# four_channel_audio_mixer.net
KiCad netlist of a schematic drawn in EAGLE
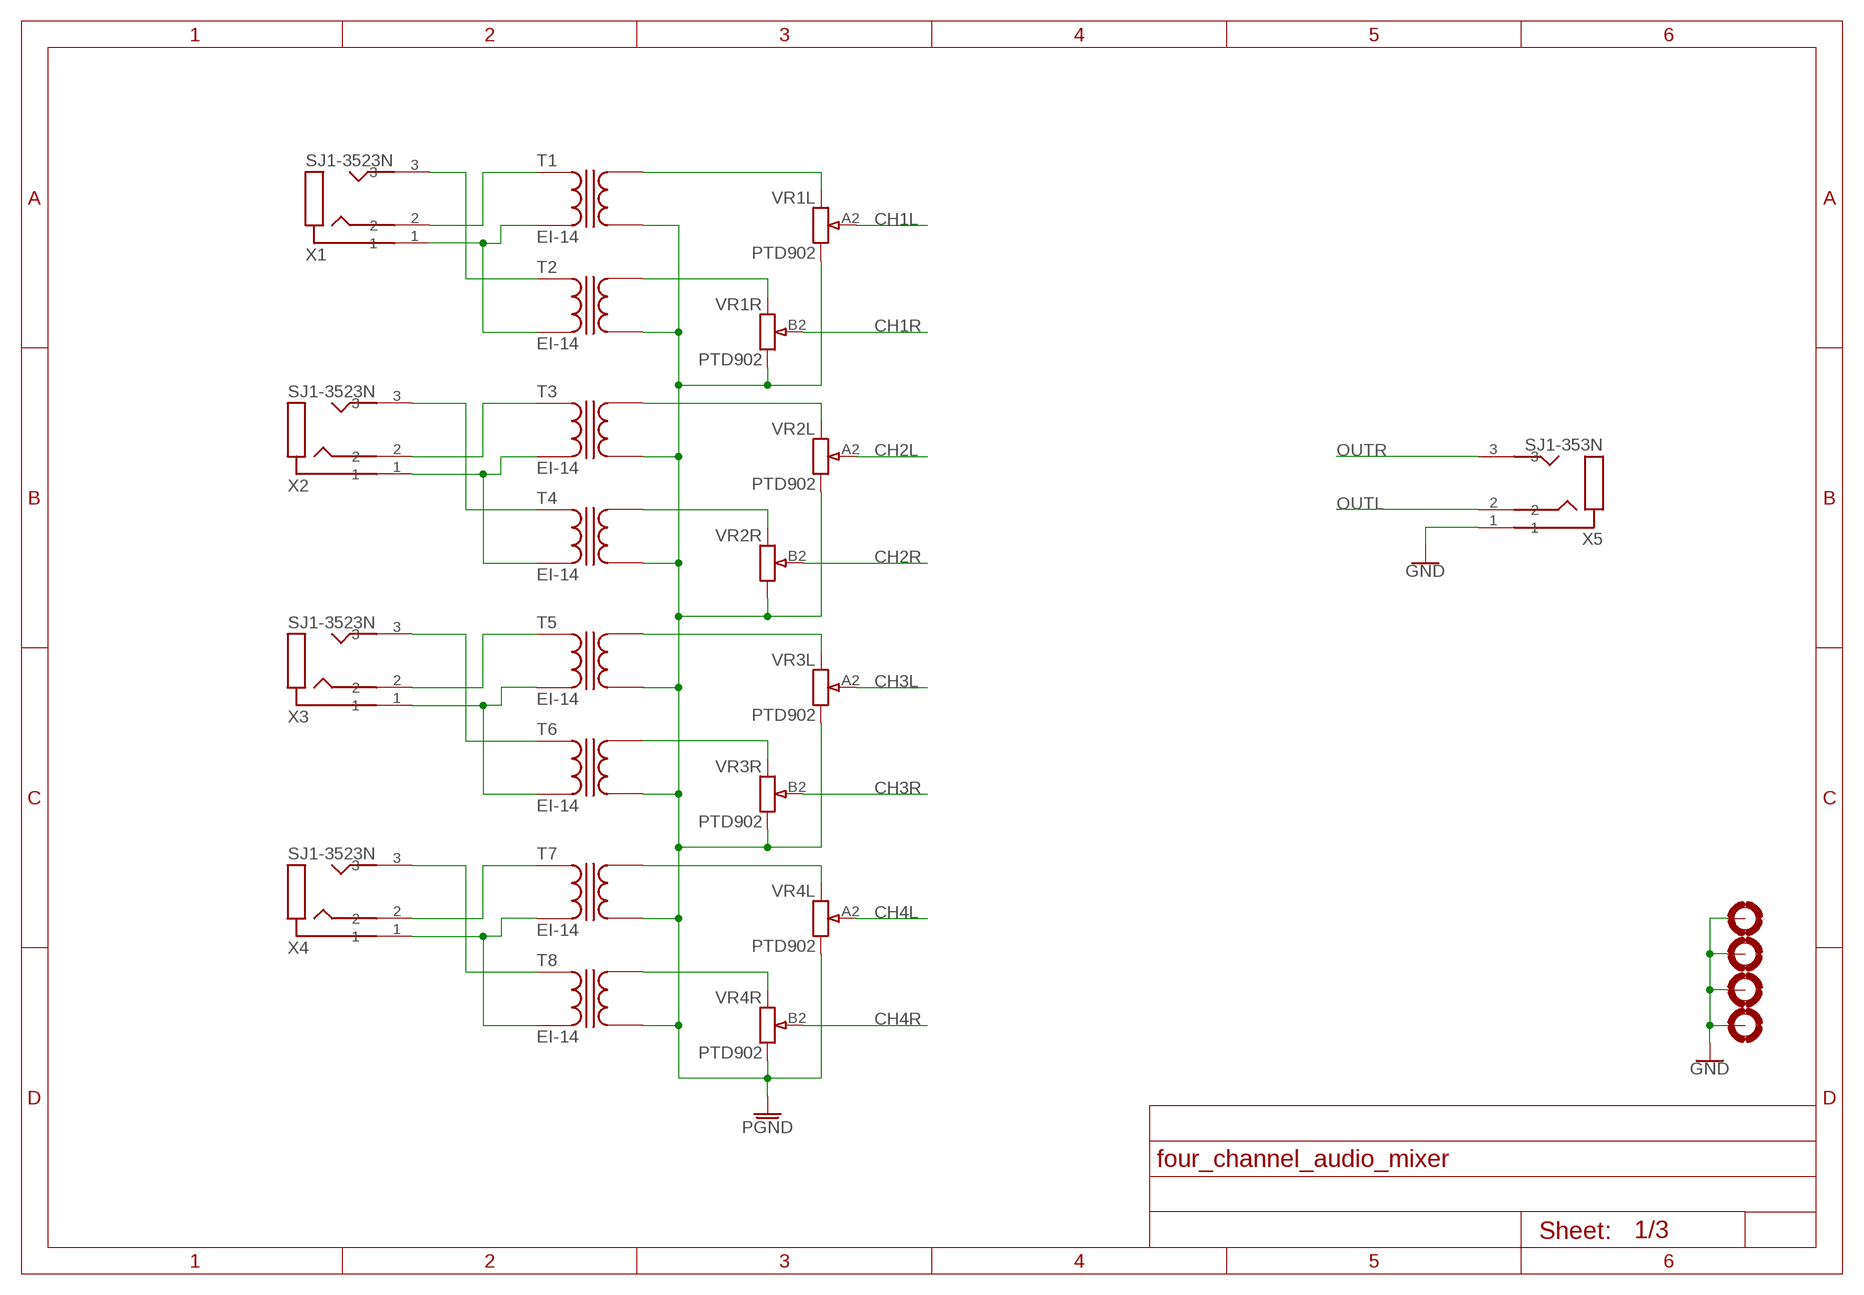
[diagram p0: schematic, sheet 1]
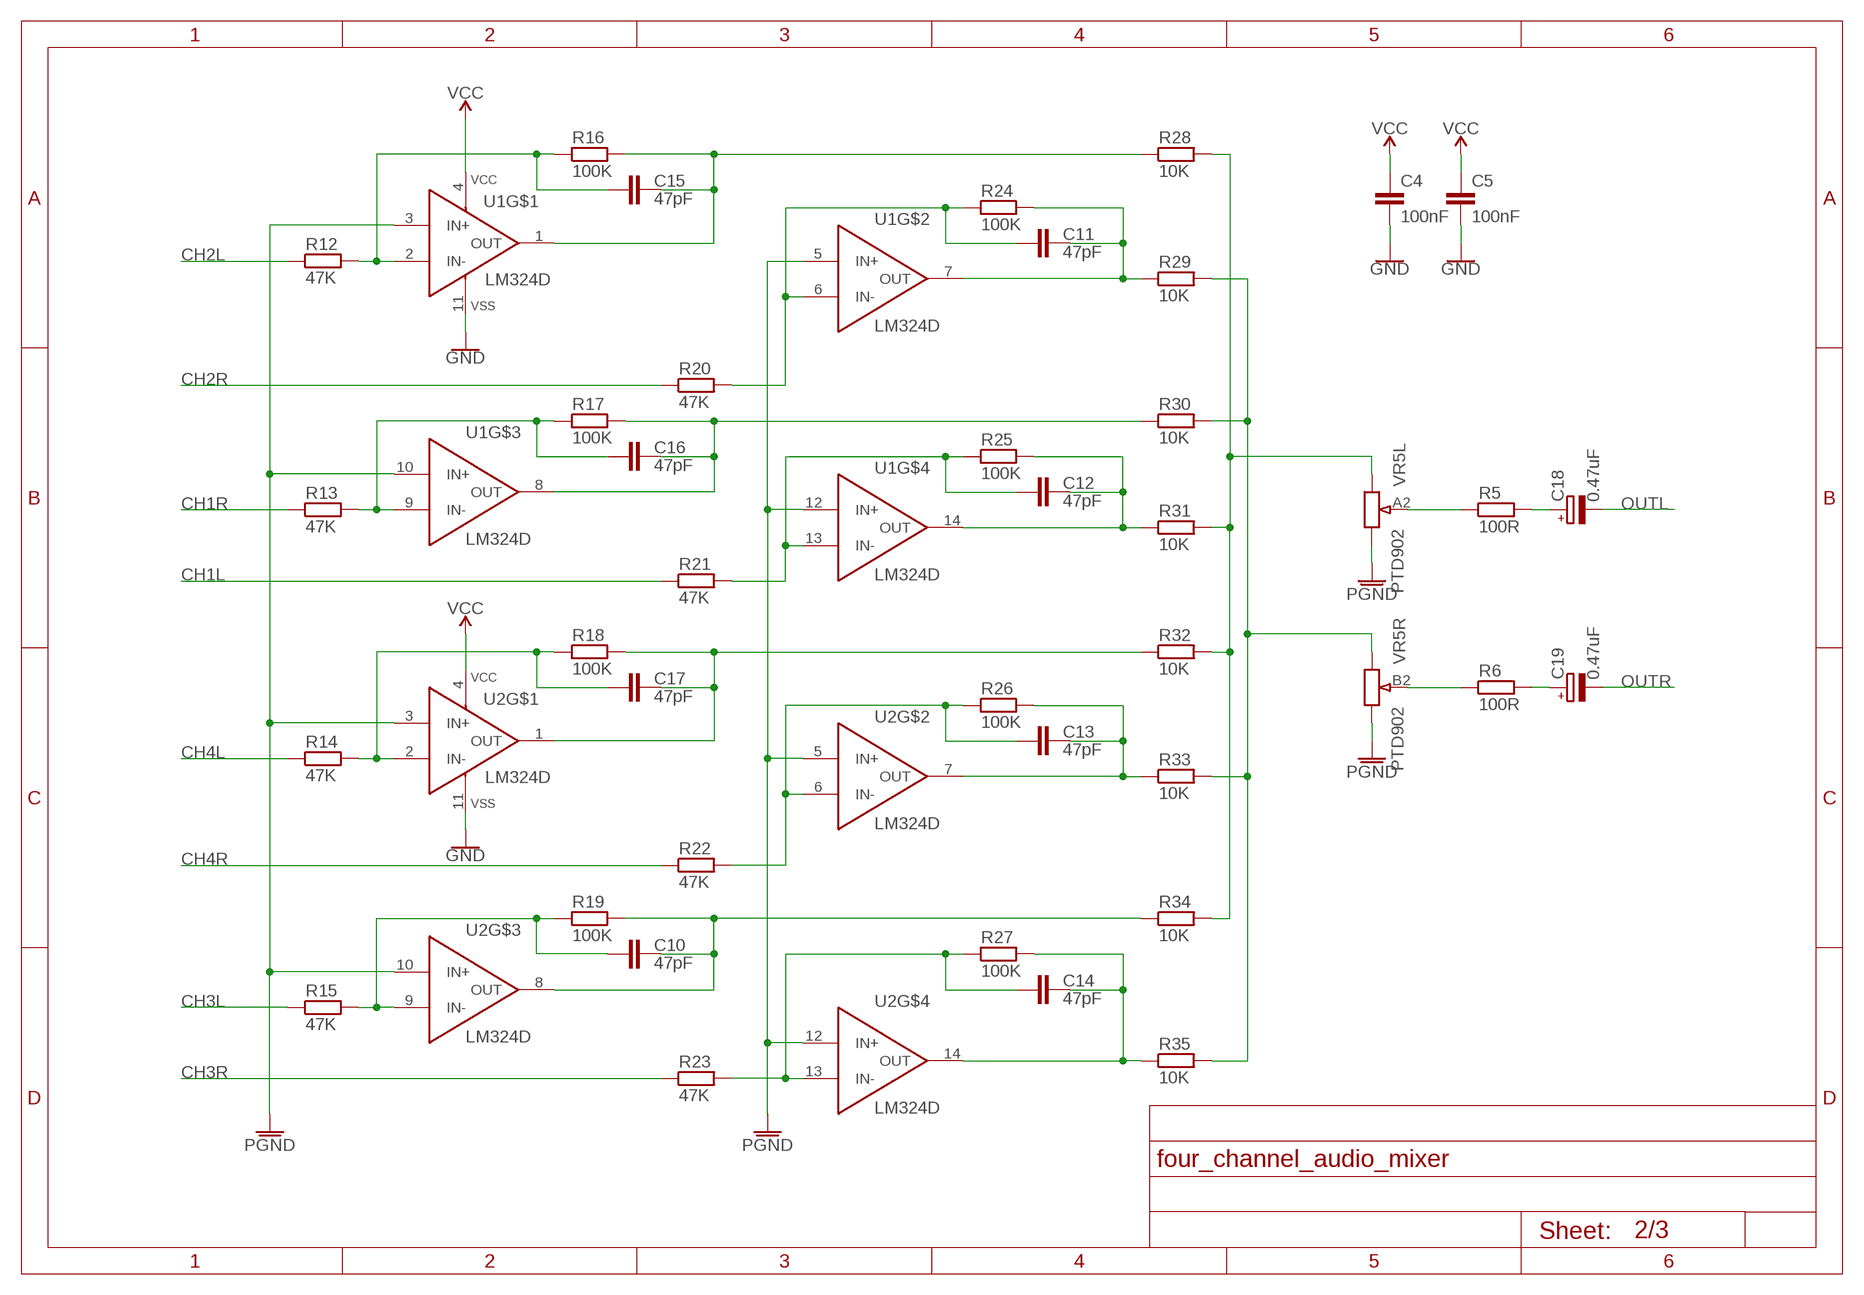
[diagram p1: schematic, sheet 2]
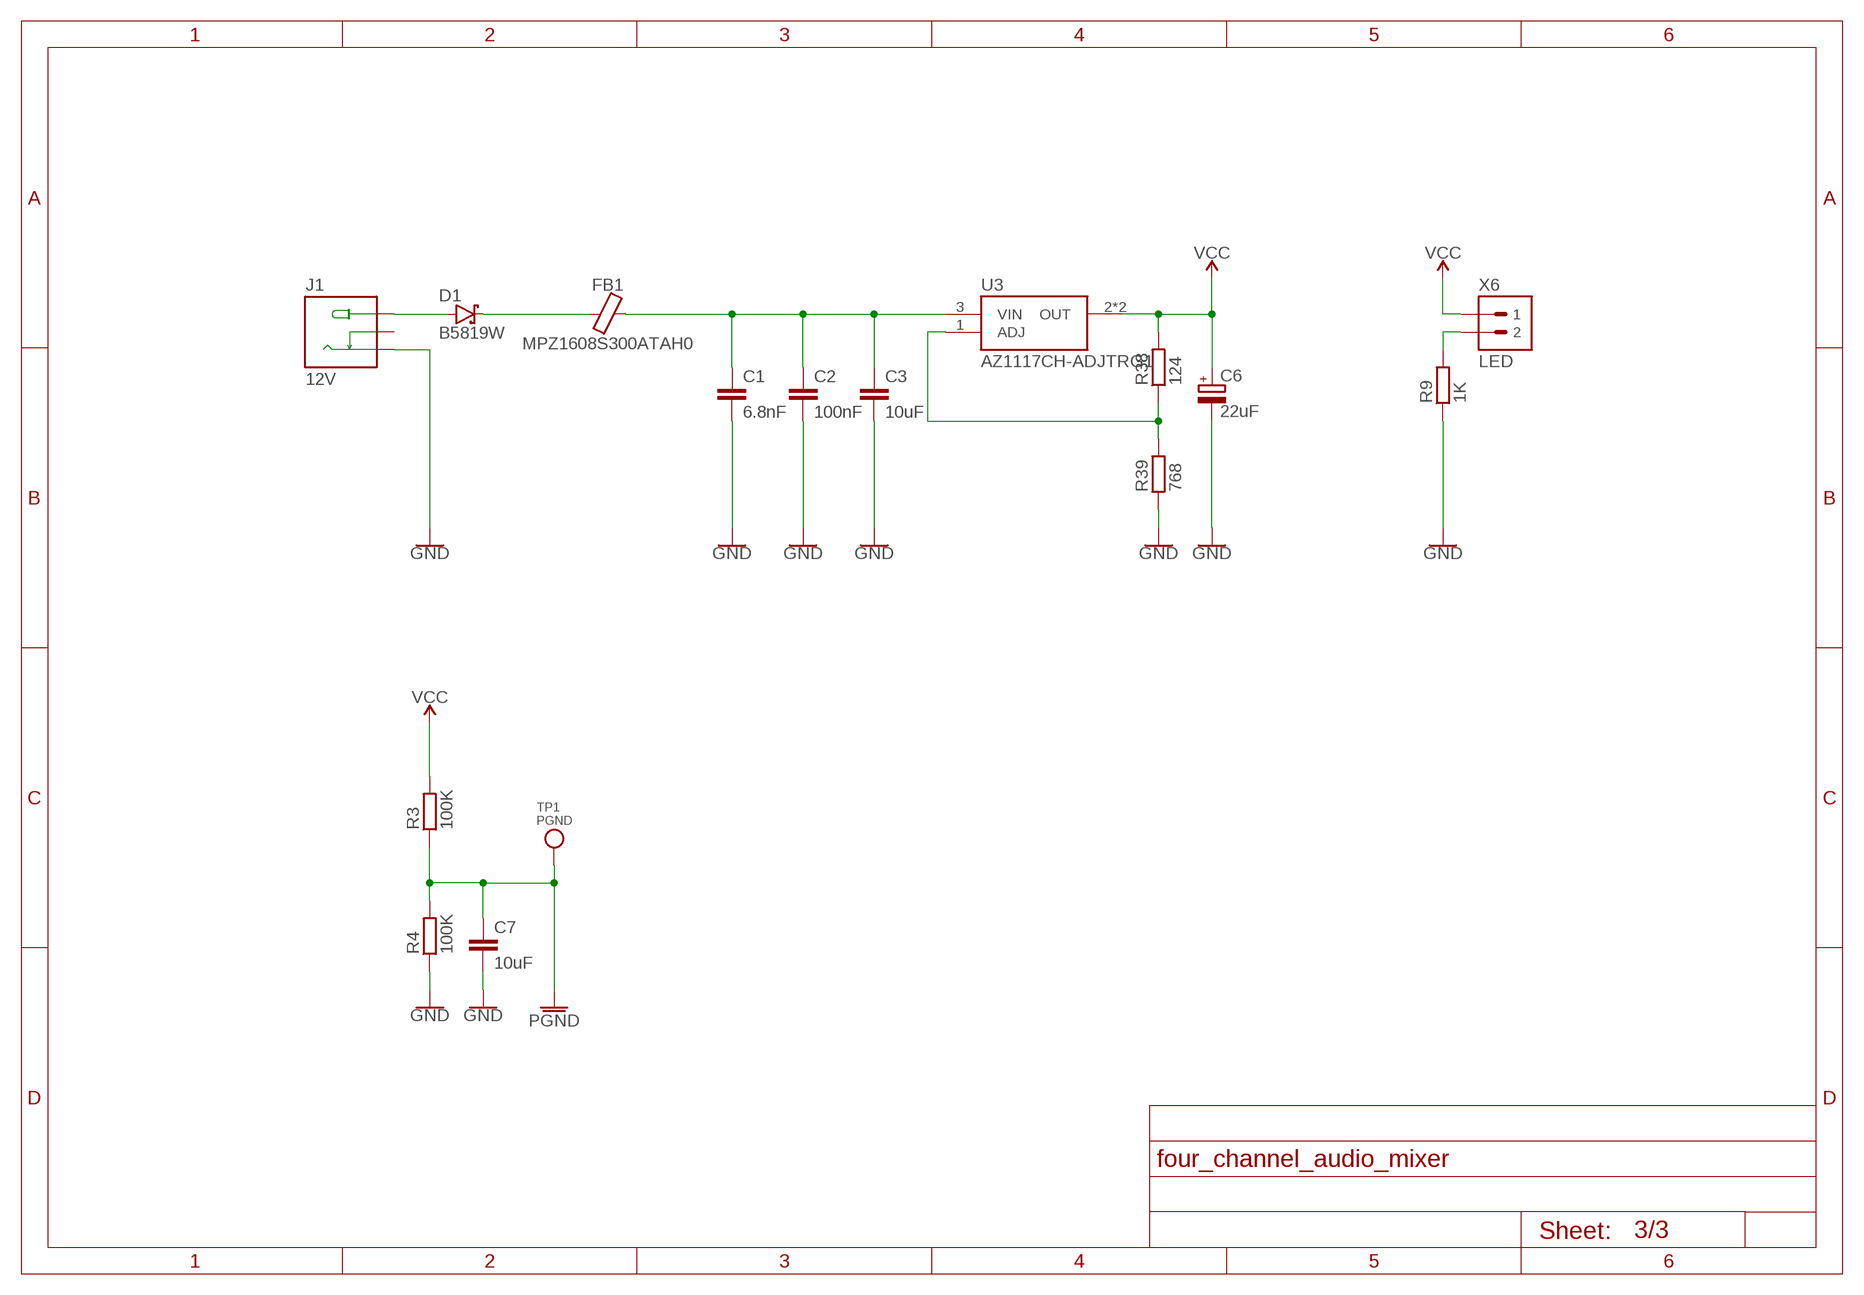
[diagram p2: schematic, sheet 3]

(export (version "E")
  (design (tool "Eeschema 10.0.6"))
  (components
    (comp (ref "H1")
      (value "MOUNTHOLE-PAD3.2")
      (footprint "eagle-import:3.2-PAD")
      (libsource (lib "eagle-import") (part "MOUNTHOLE-PAD3.2"))
    )
    (comp (ref "H2")
      (value "MOUNTHOLE-PAD3.2")
      (footprint "eagle-import:3.2-PAD")
      (libsource (lib "eagle-import") (part "MOUNTHOLE-PAD3.2"))
    )
    (comp (ref "H3")
      (value "MOUNTHOLE-PAD3.2")
      (footprint "eagle-import:3.2-PAD")
      (libsource (lib "eagle-import") (part "MOUNTHOLE-PAD3.2"))
    )
    (comp (ref "H4")
      (value "MOUNTHOLE-PAD3.2")
      (footprint "eagle-import:3.2-PAD")
      (libsource (lib "eagle-import") (part "MOUNTHOLE-PAD3.2"))
    )
    (comp (ref "T1")
      (value "EI-14")
      (footprint "eagle-import:TRANSFORMER_EI14")
      (libsource (lib "eagle-import") (part "TRANSFORMEREI14"))
    )
    (comp (ref "T2")
      (value "EI-14")
      (footprint "eagle-import:TRANSFORMER_EI14")
      (libsource (lib "eagle-import") (part "TRANSFORMEREI14"))
    )
    (comp (ref "T3")
      (value "EI-14")
      (footprint "eagle-import:TRANSFORMER_EI14")
      (libsource (lib "eagle-import") (part "TRANSFORMEREI14"))
    )
    (comp (ref "T4")
      (value "EI-14")
      (footprint "eagle-import:TRANSFORMER_EI14")
      (libsource (lib "eagle-import") (part "TRANSFORMEREI14"))
    )
    (comp (ref "T5")
      (value "EI-14")
      (footprint "eagle-import:TRANSFORMER_EI14")
      (libsource (lib "eagle-import") (part "TRANSFORMEREI14"))
    )
    (comp (ref "T6")
      (value "EI-14")
      (footprint "eagle-import:TRANSFORMER_EI14")
      (libsource (lib "eagle-import") (part "TRANSFORMEREI14"))
    )
    (comp (ref "T7")
      (value "EI-14")
      (footprint "eagle-import:TRANSFORMER_EI14")
      (libsource (lib "eagle-import") (part "TRANSFORMEREI14"))
    )
    (comp (ref "T8")
      (value "EI-14")
      (footprint "eagle-import:TRANSFORMER_EI14")
      (libsource (lib "eagle-import") (part "TRANSFORMEREI14"))
    )
    (comp (ref "VR1")
      (value "PTD902")
      (footprint "eagle-import:POT-PTD902")
      (libsource (lib "eagle-import") (part "POT-PTD902"))
    )
    (comp (ref "VR2")
      (value "PTD902")
      (footprint "eagle-import:POT-PTD902")
      (libsource (lib "eagle-import") (part "POT-PTD902"))
    )
    (comp (ref "VR3")
      (value "PTD902")
      (footprint "eagle-import:POT-PTD902")
      (libsource (lib "eagle-import") (part "POT-PTD902"))
    )
    (comp (ref "VR4")
      (value "PTD902")
      (footprint "eagle-import:POT-PTD902")
      (libsource (lib "eagle-import") (part "POT-PTD902"))
    )
    (comp (ref "X1")
      (value "SJ1-3523N")
      (footprint "eagle-import:AUDIO-3.5-SJ1-3523N")
      (libsource (lib "eagle-import") (part "AUDIO-3.5-SJ1-3523N"))
    )
    (comp (ref "X2")
      (value "SJ1-3523N")
      (footprint "eagle-import:AUDIO-3.5-SJ1-3523N")
      (libsource (lib "eagle-import") (part "AUDIO-3.5-SJ1-3523N"))
    )
    (comp (ref "X3")
      (value "SJ1-3523N")
      (footprint "eagle-import:AUDIO-3.5-SJ1-3523N")
      (libsource (lib "eagle-import") (part "AUDIO-3.5-SJ1-3523N"))
    )
    (comp (ref "X4")
      (value "SJ1-3523N")
      (footprint "eagle-import:AUDIO-3.5-SJ1-3523N")
      (libsource (lib "eagle-import") (part "AUDIO-3.5-SJ1-3523N"))
    )
    (comp (ref "X5")
      (value "SJ1-353N")
      (footprint "eagle-import:AUDIO-3.5-SJ1-3523N")
      (libsource (lib "eagle-import") (part "AUDIO-3.5-SJ1-3523N"))
    )
    (comp (ref "C4")
      (value "100nF")
      (footprint "eagle-import:C0603")
      (libsource (lib "eagle-import") (part "CAPC0603"))
    )
    (comp (ref "C5")
      (value "100nF")
      (footprint "eagle-import:C0603")
      (libsource (lib "eagle-import") (part "CAPC0603"))
    )
    (comp (ref "C10")
      (value "47pF")
      (footprint "eagle-import:C0603")
      (libsource (lib "eagle-import") (part "CAPC0603"))
    )
    (comp (ref "C11")
      (value "47pF")
      (footprint "eagle-import:C0603")
      (libsource (lib "eagle-import") (part "CAPC0603"))
    )
    (comp (ref "C12")
      (value "47pF")
      (footprint "eagle-import:C0603")
      (libsource (lib "eagle-import") (part "CAPC0603"))
    )
    (comp (ref "C13")
      (value "47pF")
      (footprint "eagle-import:C0603")
      (libsource (lib "eagle-import") (part "CAPC0603"))
    )
    (comp (ref "C14")
      (value "47pF")
      (footprint "eagle-import:C0603")
      (libsource (lib "eagle-import") (part "CAPC0603"))
    )
    (comp (ref "C15")
      (value "47pF")
      (footprint "eagle-import:C0603")
      (libsource (lib "eagle-import") (part "CAPC0603"))
    )
    (comp (ref "C16")
      (value "47pF")
      (footprint "eagle-import:C0603")
      (libsource (lib "eagle-import") (part "CAPC0603"))
    )
    (comp (ref "C17")
      (value "47pF")
      (footprint "eagle-import:C0603")
      (libsource (lib "eagle-import") (part "CAPC0603"))
    )
    (comp (ref "C18")
      (value "0.47uF")
      (footprint "eagle-import:WE-4.0X5.5")
      (libsource (lib "eagle-import") (part "CAP-POL-ALUMWURTH-4.0X5.5"))
    )
    (comp (ref "C19")
      (value "0.47uF")
      (footprint "eagle-import:WE-4.0X5.5")
      (libsource (lib "eagle-import") (part "CAP-POL-ALUMWURTH-4.0X5.5"))
    )
    (comp (ref "R5")
      (value "100R")
      (footprint "eagle-import:R0603")
      (libsource (lib "eagle-import") (part "RESISTOR0603"))
    )
    (comp (ref "R6")
      (value "100R")
      (footprint "eagle-import:R0603")
      (libsource (lib "eagle-import") (part "RESISTOR0603"))
    )
    (comp (ref "R12")
      (value "47K")
      (footprint "eagle-import:R0603")
      (libsource (lib "eagle-import") (part "RESISTOR0603"))
    )
    (comp (ref "R13")
      (value "47K")
      (footprint "eagle-import:R0603")
      (libsource (lib "eagle-import") (part "RESISTOR0603"))
    )
    (comp (ref "R14")
      (value "47K")
      (footprint "eagle-import:R0603")
      (libsource (lib "eagle-import") (part "RESISTOR0603"))
    )
    (comp (ref "R15")
      (value "47K")
      (footprint "eagle-import:R0603")
      (libsource (lib "eagle-import") (part "RESISTOR0603"))
    )
    (comp (ref "R16")
      (value "100K")
      (footprint "eagle-import:R0603")
      (libsource (lib "eagle-import") (part "RESISTOR0603"))
    )
    (comp (ref "R17")
      (value "100K")
      (footprint "eagle-import:R0603")
      (libsource (lib "eagle-import") (part "RESISTOR0603"))
    )
    (comp (ref "R18")
      (value "100K")
      (footprint "eagle-import:R0603")
      (libsource (lib "eagle-import") (part "RESISTOR0603"))
    )
    (comp (ref "R19")
      (value "100K")
      (footprint "eagle-import:R0603")
      (libsource (lib "eagle-import") (part "RESISTOR0603"))
    )
    (comp (ref "R20")
      (value "47K")
      (footprint "eagle-import:R0603")
      (libsource (lib "eagle-import") (part "RESISTOR0603"))
    )
    (comp (ref "R21")
      (value "47K")
      (footprint "eagle-import:R0603")
      (libsource (lib "eagle-import") (part "RESISTOR0603"))
    )
    (comp (ref "R22")
      (value "47K")
      (footprint "eagle-import:R0603")
      (libsource (lib "eagle-import") (part "RESISTOR0603"))
    )
    (comp (ref "R23")
      (value "47K")
      (footprint "eagle-import:R0603")
      (libsource (lib "eagle-import") (part "RESISTOR0603"))
    )
    (comp (ref "R24")
      (value "100K")
      (footprint "eagle-import:R0603")
      (libsource (lib "eagle-import") (part "RESISTOR0603"))
    )
    (comp (ref "R25")
      (value "100K")
      (footprint "eagle-import:R0603")
      (libsource (lib "eagle-import") (part "RESISTOR0603"))
    )
    (comp (ref "R26")
      (value "100K")
      (footprint "eagle-import:R0603")
      (libsource (lib "eagle-import") (part "RESISTOR0603"))
    )
    (comp (ref "R27")
      (value "100K")
      (footprint "eagle-import:R0603")
      (libsource (lib "eagle-import") (part "RESISTOR0603"))
    )
    (comp (ref "R28")
      (value "10K")
      (footprint "eagle-import:R0603")
      (libsource (lib "eagle-import") (part "RESISTOR0603"))
    )
    (comp (ref "R29")
      (value "10K")
      (footprint "eagle-import:R0603")
      (libsource (lib "eagle-import") (part "RESISTOR0603"))
    )
    (comp (ref "R30")
      (value "10K")
      (footprint "eagle-import:R0603")
      (libsource (lib "eagle-import") (part "RESISTOR0603"))
    )
    (comp (ref "R31")
      (value "10K")
      (footprint "eagle-import:R0603")
      (libsource (lib "eagle-import") (part "RESISTOR0603"))
    )
    (comp (ref "R32")
      (value "10K")
      (footprint "eagle-import:R0603")
      (libsource (lib "eagle-import") (part "RESISTOR0603"))
    )
    (comp (ref "R33")
      (value "10K")
      (footprint "eagle-import:R0603")
      (libsource (lib "eagle-import") (part "RESISTOR0603"))
    )
    (comp (ref "R34")
      (value "10K")
      (footprint "eagle-import:R0603")
      (libsource (lib "eagle-import") (part "RESISTOR0603"))
    )
    (comp (ref "R35")
      (value "10K")
      (footprint "eagle-import:R0603")
      (libsource (lib "eagle-import") (part "RESISTOR0603"))
    )
    (comp (ref "U1")
      (value "LM324D")
      (footprint "eagle-import:SOIC-14")
      (libsource (lib "eagle-import") (part "OPAMP-LM324D"))
    )
    (comp (ref "U2")
      (value "LM324D")
      (footprint "eagle-import:SOIC-14")
      (libsource (lib "eagle-import") (part "OPAMP-LM324D"))
    )
    (comp (ref "VR5")
      (value "PTD902")
      (footprint "eagle-import:POT-PTD902")
      (libsource (lib "eagle-import") (part "POT-PTD902"))
    )
    (comp (ref "C1")
      (value "6.8nF")
      (footprint "eagle-import:C0603")
      (libsource (lib "eagle-import") (part "CAPC0603"))
    )
    (comp (ref "C2")
      (value "100nF")
      (footprint "eagle-import:C0603")
      (libsource (lib "eagle-import") (part "CAPC0603"))
    )
    (comp (ref "C3")
      (value "10uF")
      (footprint "eagle-import:C0603")
      (libsource (lib "eagle-import") (part "CAPC0603"))
    )
    (comp (ref "C6")
      (value "22uF")
      (footprint "eagle-import:CASE-B-3528")
      (libsource (lib "eagle-import") (part "CAP-TANT-HUNANB-3528"))
    )
    (comp (ref "C7")
      (value "10uF")
      (footprint "eagle-import:C0603")
      (libsource (lib "eagle-import") (part "CAPC0603"))
    )
    (comp (ref "D1")
      (value "B5819W")
      (footprint "eagle-import:SOD-123")
      (libsource (lib "eagle-import") (part "DIODE-SCHOTTKYSOD-123"))
    )
    (comp (ref "FB1")
      (value "MPZ1608S300ATAH0")
      (footprint "eagle-import:MPZ1608")
      (libsource (lib "eagle-import") (part "BEADMPZ1608"))
    )
    (comp (ref "J1")
      (value "12V")
      (footprint "eagle-import:5DJ20DC02-03T0BLB-01-14.5X10.7.0X9.0MM")
      (libsource (lib "eagle-import") (part "CONN-POWER-JACK-2.1MM(DC-005)5DJ20DC02"))
    )
    (comp (ref "R3")
      (value "100K")
      (footprint "eagle-import:R0603")
      (libsource (lib "eagle-import") (part "RESISTOR0603"))
    )
    (comp (ref "R4")
      (value "100K")
      (footprint "eagle-import:R0603")
      (libsource (lib "eagle-import") (part "RESISTOR0603"))
    )
    (comp (ref "R9")
      (value "1K")
      (footprint "eagle-import:R0603")
      (libsource (lib "eagle-import") (part "RESISTOR0603"))
    )
    (comp (ref "R38")
      (value "124")
      (footprint "eagle-import:R0603")
      (libsource (lib "eagle-import") (part "RESISTOR0603"))
    )
    (comp (ref "R39")
      (value "768")
      (footprint "eagle-import:R0603")
      (libsource (lib "eagle-import") (part "RESISTOR0603"))
    )
    (comp (ref "TP1")
      (value "PGND")
      (footprint "eagle-import:1X01_ROUND")
      (libsource (lib "eagle-import") (part "TESTPOINT0.1{dblquote}"))
    )
    (comp (ref "U3")
      (value "AZ1117CH-ADJTRG1")
      (footprint "eagle-import:SOT-223")
      (libsource (lib "eagle-import") (part "DIODES-AZ1117CH-ADJTRG1"))
    )
    (comp (ref "X6")
      (value "LED")
      (footprint "eagle-import:1X02P-2.54")
      (libsource (lib "eagle-import") (part "HEADER-1X02-2.54POL"))
    )
  )
  (nets
    (net (code "1") (name "CH1L") (class "Default")
      (node (ref "R21") (pin "1") (pinfunction "1_1") (pintype "passive"))
      (node (ref "VR1") (pin "A2") (pinfunction "2_A2") (pintype "bidirectional"))
    )
    (net (code "2") (name "CH1R") (class "Default")
      (node (ref "R13") (pin "1") (pinfunction "1_1") (pintype "passive"))
      (node (ref "VR1") (pin "B2") (pinfunction "2_B2") (pintype "bidirectional"))
    )
    (net (code "3") (name "CH2L") (class "Default")
      (node (ref "R12") (pin "1") (pinfunction "1_1") (pintype "passive"))
      (node (ref "VR2") (pin "A2") (pinfunction "2_A2") (pintype "bidirectional"))
    )
    (net (code "4") (name "CH2R") (class "Default")
      (node (ref "R20") (pin "1") (pinfunction "1_1") (pintype "passive"))
      (node (ref "VR2") (pin "B2") (pinfunction "2_B2") (pintype "bidirectional"))
    )
    (net (code "5") (name "CH3L") (class "Default")
      (node (ref "R15") (pin "1") (pinfunction "1_1") (pintype "passive"))
      (node (ref "VR3") (pin "A2") (pinfunction "2_A2") (pintype "bidirectional"))
    )
    (net (code "6") (name "CH3R") (class "Default")
      (node (ref "R23") (pin "1") (pinfunction "1_1") (pintype "passive"))
      (node (ref "VR3") (pin "B2") (pinfunction "2_B2") (pintype "bidirectional"))
    )
    (net (code "7") (name "CH4L") (class "Default")
      (node (ref "R14") (pin "1") (pinfunction "1_1") (pintype "passive"))
      (node (ref "VR4") (pin "A2") (pinfunction "2_A2") (pintype "bidirectional"))
    )
    (net (code "8") (name "CH4R") (class "Default")
      (node (ref "R22") (pin "1") (pinfunction "1_1") (pintype "passive"))
      (node (ref "VR4") (pin "B2") (pinfunction "2_B2") (pintype "bidirectional"))
    )
    (net (code "9") (name "GND") (class "Default")
      (node (ref "C1") (pin "2") (pinfunction "2_2") (pintype "passive"))
      (node (ref "C2") (pin "2") (pinfunction "2_2") (pintype "passive"))
      (node (ref "C3") (pin "2") (pinfunction "2_2") (pintype "passive"))
      (node (ref "C4") (pin "2") (pinfunction "2_2") (pintype "passive"))
      (node (ref "C5") (pin "2") (pinfunction "2_2") (pintype "passive"))
      (node (ref "C6") (pin "-") (pinfunction "-_-") (pintype "passive"))
      (node (ref "C7") (pin "2") (pinfunction "2_2") (pintype "passive"))
      (node (ref "H1") (pin "B3,2") (pinfunction "MOUNT_B3,2") (pintype "passive"))
      (node (ref "H2") (pin "B3,2") (pinfunction "MOUNT_B3,2") (pintype "passive"))
      (node (ref "H3") (pin "B3,2") (pinfunction "MOUNT_B3,2") (pintype "passive"))
      (node (ref "H4") (pin "B3,2") (pinfunction "MOUNT_B3,2") (pintype "passive"))
      (node (ref "J1") (pin "-1") (pinfunction "-_-1") (pintype "bidirectional"))
      (node (ref "R39") (pin "1") (pinfunction "1_1") (pintype "passive"))
      (node (ref "R4") (pin "1") (pinfunction "1_1") (pintype "passive"))
      (node (ref "R9") (pin "1") (pinfunction "1_1") (pintype "passive"))
      (node (ref "U1") (pin "11") (pinfunction "VSS_11") (pintype "bidirectional"))
      (node (ref "U2") (pin "11") (pinfunction "VSS_11") (pintype "bidirectional"))
      (node (ref "X5") (pin "1") (pinfunction "1_1") (pintype "bidirectional"))
    )
    (net (code "10") (name "Net-(C18-Pad+)") (class "Default")
      (node (ref "C18") (pin "+") (pinfunction "+_+") (pintype "passive"))
      (node (ref "R5") (pin "2") (pinfunction "2_2") (pintype "passive"))
    )
    (net (code "11") (name "Net-(C19-Pad+)") (class "Default")
      (node (ref "C19") (pin "+") (pinfunction "+_+") (pintype "passive"))
      (node (ref "R6") (pin "2") (pinfunction "2_2") (pintype "passive"))
    )
    (net (code "12") (name "Net-(D1-PadA)") (class "Default")
      (node (ref "D1") (pin "A") (pinfunction "A_A") (pintype "passive"))
      (node (ref "J1") (pin "+") (pinfunction "+_+") (pintype "bidirectional"))
    )
    (net (code "13") (name "Net-(D1-PadC)") (class "Default")
      (node (ref "D1") (pin "C") (pinfunction "C_C") (pintype "passive"))
      (node (ref "FB1") (pin "1") (pinfunction "1_1") (pintype "bidirectional"))
    )
    (net (code "14") (name "Net-(R9-Pad2)") (class "Default")
      (node (ref "R9") (pin "2") (pinfunction "2_2") (pintype "passive"))
      (node (ref "X6") (pin "2") (pinfunction "2_2") (pintype "passive"))
    )
    (net (code "15") (name "Net-(T1-PadA1)") (class "Default")
      (node (ref "T1") (pin "A1") (pinfunction "A1_A1") (pintype "bidirectional"))
      (node (ref "X1") (pin "2") (pinfunction "2_2") (pintype "bidirectional"))
    )
    (net (code "16") (name "Net-(T1-PadA2)") (class "Default")
      (node (ref "T1") (pin "A2") (pinfunction "A2_A2") (pintype "bidirectional"))
      (node (ref "T2") (pin "A2") (pinfunction "A2_A2") (pintype "bidirectional"))
      (node (ref "X1") (pin "1") (pinfunction "1_1") (pintype "bidirectional"))
    )
    (net (code "17") (name "Net-(T2-PadA1)") (class "Default")
      (node (ref "T2") (pin "A1") (pinfunction "A1_A1") (pintype "bidirectional"))
      (node (ref "X1") (pin "3") (pinfunction "3_3") (pintype "bidirectional"))
    )
    (net (code "18") (name "Net-(T3-PadA1)") (class "Default")
      (node (ref "T3") (pin "A1") (pinfunction "A1_A1") (pintype "bidirectional"))
      (node (ref "X2") (pin "2") (pinfunction "2_2") (pintype "bidirectional"))
    )
    (net (code "19") (name "Net-(T3-PadA2)") (class "Default")
      (node (ref "T3") (pin "A2") (pinfunction "A2_A2") (pintype "bidirectional"))
      (node (ref "T4") (pin "A2") (pinfunction "A2_A2") (pintype "bidirectional"))
      (node (ref "X2") (pin "1") (pinfunction "1_1") (pintype "bidirectional"))
    )
    (net (code "20") (name "Net-(T4-PadA1)") (class "Default")
      (node (ref "T4") (pin "A1") (pinfunction "A1_A1") (pintype "bidirectional"))
      (node (ref "X2") (pin "3") (pinfunction "3_3") (pintype "bidirectional"))
    )
    (net (code "21") (name "Net-(T5-PadA1)") (class "Default")
      (node (ref "T5") (pin "A1") (pinfunction "A1_A1") (pintype "bidirectional"))
      (node (ref "X3") (pin "2") (pinfunction "2_2") (pintype "bidirectional"))
    )
    (net (code "22") (name "Net-(T5-PadA2)") (class "Default")
      (node (ref "T5") (pin "A2") (pinfunction "A2_A2") (pintype "bidirectional"))
      (node (ref "T6") (pin "A2") (pinfunction "A2_A2") (pintype "bidirectional"))
      (node (ref "X3") (pin "1") (pinfunction "1_1") (pintype "bidirectional"))
    )
    (net (code "23") (name "Net-(T6-PadA1)") (class "Default")
      (node (ref "T6") (pin "A1") (pinfunction "A1_A1") (pintype "bidirectional"))
      (node (ref "X3") (pin "3") (pinfunction "3_3") (pintype "bidirectional"))
    )
    (net (code "24") (name "Net-(T7-PadA1)") (class "Default")
      (node (ref "T7") (pin "A1") (pinfunction "A1_A1") (pintype "bidirectional"))
      (node (ref "X4") (pin "2") (pinfunction "2_2") (pintype "bidirectional"))
    )
    (net (code "25") (name "Net-(T7-PadA2)") (class "Default")
      (node (ref "T7") (pin "A2") (pinfunction "A2_A2") (pintype "bidirectional"))
      (node (ref "T8") (pin "A2") (pinfunction "A2_A2") (pintype "bidirectional"))
      (node (ref "X4") (pin "1") (pinfunction "1_1") (pintype "bidirectional"))
    )
    (net (code "26") (name "Net-(T8-PadA1)") (class "Default")
      (node (ref "T8") (pin "A1") (pinfunction "A1_A1") (pintype "bidirectional"))
      (node (ref "X4") (pin "3") (pinfunction "3_3") (pintype "bidirectional"))
    )
    (net (code "27") (name "Net-(U1A-IN-)") (class "Default")
      (node (ref "C15") (pin "2") (pinfunction "2_2") (pintype "passive"))
      (node (ref "R12") (pin "2") (pinfunction "2_2") (pintype "passive"))
      (node (ref "R16") (pin "1") (pinfunction "1_1") (pintype "passive"))
      (node (ref "U1") (pin "2") (pinfunction "IN-_2") (pintype "bidirectional"))
    )
    (net (code "28") (name "Net-(U1A-OUT)") (class "Default")
      (node (ref "C15") (pin "1") (pinfunction "1_1") (pintype "passive"))
      (node (ref "R16") (pin "2") (pinfunction "2_2") (pintype "passive"))
      (node (ref "R28") (pin "1") (pinfunction "1_1") (pintype "passive"))
      (node (ref "U1") (pin "1") (pinfunction "OUT_1") (pintype "bidirectional"))
    )
    (net (code "29") (name "Net-(U1B-IN-)") (class "Default")
      (node (ref "C11") (pin "2") (pinfunction "2_2") (pintype "passive"))
      (node (ref "R20") (pin "2") (pinfunction "2_2") (pintype "passive"))
      (node (ref "R24") (pin "1") (pinfunction "1_1") (pintype "passive"))
      (node (ref "U1") (pin "6") (pinfunction "IN-_6") (pintype "bidirectional"))
    )
    (net (code "30") (name "Net-(U1B-OUT)") (class "Default")
      (node (ref "C11") (pin "1") (pinfunction "1_1") (pintype "passive"))
      (node (ref "R24") (pin "2") (pinfunction "2_2") (pintype "passive"))
      (node (ref "R29") (pin "1") (pinfunction "1_1") (pintype "passive"))
      (node (ref "U1") (pin "7") (pinfunction "OUT_7") (pintype "bidirectional"))
    )
    (net (code "31") (name "Net-(U1C-IN-)") (class "Default")
      (node (ref "C16") (pin "2") (pinfunction "2_2") (pintype "passive"))
      (node (ref "R13") (pin "2") (pinfunction "2_2") (pintype "passive"))
      (node (ref "R17") (pin "1") (pinfunction "1_1") (pintype "passive"))
      (node (ref "U1") (pin "9") (pinfunction "IN-_9") (pintype "bidirectional"))
    )
    (net (code "32") (name "Net-(U1C-OUT)") (class "Default")
      (node (ref "C16") (pin "1") (pinfunction "1_1") (pintype "passive"))
      (node (ref "R17") (pin "2") (pinfunction "2_2") (pintype "passive"))
      (node (ref "R30") (pin "1") (pinfunction "1_1") (pintype "passive"))
      (node (ref "U1") (pin "8") (pinfunction "OUT_8") (pintype "bidirectional"))
    )
    (net (code "33") (name "Net-(U1D-IN-)") (class "Default")
      (node (ref "C12") (pin "2") (pinfunction "2_2") (pintype "passive"))
      (node (ref "R21") (pin "2") (pinfunction "2_2") (pintype "passive"))
      (node (ref "R25") (pin "1") (pinfunction "1_1") (pintype "passive"))
      (node (ref "U1") (pin "13") (pinfunction "IN-_13") (pintype "bidirectional"))
    )
    (net (code "34") (name "Net-(U1D-OUT)") (class "Default")
      (node (ref "C12") (pin "1") (pinfunction "1_1") (pintype "passive"))
      (node (ref "R25") (pin "2") (pinfunction "2_2") (pintype "passive"))
      (node (ref "R31") (pin "1") (pinfunction "1_1") (pintype "passive"))
      (node (ref "U1") (pin "14") (pinfunction "OUT_14") (pintype "bidirectional"))
    )
    (net (code "35") (name "Net-(U2A-IN-)") (class "Default")
      (node (ref "C17") (pin "2") (pinfunction "2_2") (pintype "passive"))
      (node (ref "R14") (pin "2") (pinfunction "2_2") (pintype "passive"))
      (node (ref "R18") (pin "1") (pinfunction "1_1") (pintype "passive"))
      (node (ref "U2") (pin "2") (pinfunction "IN-_2") (pintype "bidirectional"))
    )
    (net (code "36") (name "Net-(U2A-OUT)") (class "Default")
      (node (ref "C17") (pin "1") (pinfunction "1_1") (pintype "passive"))
      (node (ref "R18") (pin "2") (pinfunction "2_2") (pintype "passive"))
      (node (ref "R32") (pin "1") (pinfunction "1_1") (pintype "passive"))
      (node (ref "U2") (pin "1") (pinfunction "OUT_1") (pintype "bidirectional"))
    )
    (net (code "37") (name "Net-(U2B-IN-)") (class "Default")
      (node (ref "C13") (pin "2") (pinfunction "2_2") (pintype "passive"))
      (node (ref "R22") (pin "2") (pinfunction "2_2") (pintype "passive"))
      (node (ref "R26") (pin "1") (pinfunction "1_1") (pintype "passive"))
      (node (ref "U2") (pin "6") (pinfunction "IN-_6") (pintype "bidirectional"))
    )
    (net (code "38") (name "Net-(U2B-OUT)") (class "Default")
      (node (ref "C13") (pin "1") (pinfunction "1_1") (pintype "passive"))
      (node (ref "R26") (pin "2") (pinfunction "2_2") (pintype "passive"))
      (node (ref "R33") (pin "1") (pinfunction "1_1") (pintype "passive"))
      (node (ref "U2") (pin "7") (pinfunction "OUT_7") (pintype "bidirectional"))
    )
    (net (code "39") (name "Net-(U2C-IN-)") (class "Default")
      (node (ref "C10") (pin "2") (pinfunction "2_2") (pintype "passive"))
      (node (ref "R15") (pin "2") (pinfunction "2_2") (pintype "passive"))
      (node (ref "R19") (pin "1") (pinfunction "1_1") (pintype "passive"))
      (node (ref "U2") (pin "9") (pinfunction "IN-_9") (pintype "bidirectional"))
    )
    (net (code "40") (name "Net-(U2C-OUT)") (class "Default")
      (node (ref "C10") (pin "1") (pinfunction "1_1") (pintype "passive"))
      (node (ref "R19") (pin "2") (pinfunction "2_2") (pintype "passive"))
      (node (ref "R34") (pin "1") (pinfunction "1_1") (pintype "passive"))
      (node (ref "U2") (pin "8") (pinfunction "OUT_8") (pintype "bidirectional"))
    )
    (net (code "41") (name "Net-(U2D-IN-)") (class "Default")
      (node (ref "C14") (pin "2") (pinfunction "2_2") (pintype "passive"))
      (node (ref "R23") (pin "2") (pinfunction "2_2") (pintype "passive"))
      (node (ref "R27") (pin "1") (pinfunction "1_1") (pintype "passive"))
      (node (ref "U2") (pin "13") (pinfunction "IN-_13") (pintype "bidirectional"))
    )
    (net (code "42") (name "Net-(U2D-OUT)") (class "Default")
      (node (ref "C14") (pin "1") (pinfunction "1_1") (pintype "passive"))
      (node (ref "R27") (pin "2") (pinfunction "2_2") (pintype "passive"))
      (node (ref "R35") (pin "1") (pinfunction "1_1") (pintype "passive"))
      (node (ref "U2") (pin "14") (pinfunction "OUT_14") (pintype "bidirectional"))
    )
    (net (code "43") (name "Net-(U3-ADJ)") (class "Default")
      (node (ref "R38") (pin "1") (pinfunction "1_1") (pintype "passive"))
      (node (ref "R39") (pin "2") (pinfunction "2_2") (pintype "passive"))
      (node (ref "U3") (pin "1") (pinfunction "ADJ_1") (pintype "bidirectional"))
    )
    (net (code "44") (name "Net-(U3-VIN)") (class "Default")
      (node (ref "C1") (pin "1") (pinfunction "1_1") (pintype "passive"))
      (node (ref "C2") (pin "1") (pinfunction "1_1") (pintype "passive"))
      (node (ref "C3") (pin "1") (pinfunction "1_1") (pintype "passive"))
      (node (ref "FB1") (pin "2") (pinfunction "2_2") (pintype "bidirectional"))
      (node (ref "U3") (pin "3") (pinfunction "VIN_3") (pintype "bidirectional"))
    )
    (net (code "45") (name "Net-(VR1A-3)") (class "Default")
      (node (ref "T1") (pin "B2") (pinfunction "B2_B2") (pintype "bidirectional"))
      (node (ref "VR1") (pin "A3") (pinfunction "3_A3") (pintype "bidirectional"))
    )
    (net (code "46") (name "Net-(VR1B-3)") (class "Default")
      (node (ref "T2") (pin "B2") (pinfunction "B2_B2") (pintype "bidirectional"))
      (node (ref "VR1") (pin "B3") (pinfunction "3_B3") (pintype "bidirectional"))
    )
    (net (code "47") (name "Net-(VR2A-3)") (class "Default")
      (node (ref "T3") (pin "B2") (pinfunction "B2_B2") (pintype "bidirectional"))
      (node (ref "VR2") (pin "A3") (pinfunction "3_A3") (pintype "bidirectional"))
    )
    (net (code "48") (name "Net-(VR2B-3)") (class "Default")
      (node (ref "T4") (pin "B2") (pinfunction "B2_B2") (pintype "bidirectional"))
      (node (ref "VR2") (pin "B3") (pinfunction "3_B3") (pintype "bidirectional"))
    )
    (net (code "49") (name "Net-(VR3A-3)") (class "Default")
      (node (ref "T5") (pin "B2") (pinfunction "B2_B2") (pintype "bidirectional"))
      (node (ref "VR3") (pin "A3") (pinfunction "3_A3") (pintype "bidirectional"))
    )
    (net (code "50") (name "Net-(VR3B-3)") (class "Default")
      (node (ref "T6") (pin "B2") (pinfunction "B2_B2") (pintype "bidirectional"))
      (node (ref "VR3") (pin "B3") (pinfunction "3_B3") (pintype "bidirectional"))
    )
    (net (code "51") (name "Net-(VR4A-3)") (class "Default")
      (node (ref "T7") (pin "B2") (pinfunction "B2_B2") (pintype "bidirectional"))
      (node (ref "VR4") (pin "A3") (pinfunction "3_A3") (pintype "bidirectional"))
    )
    (net (code "52") (name "Net-(VR4B-3)") (class "Default")
      (node (ref "T8") (pin "B2") (pinfunction "B2_B2") (pintype "bidirectional"))
      (node (ref "VR4") (pin "B3") (pinfunction "3_B3") (pintype "bidirectional"))
    )
    (net (code "53") (name "Net-(VR5A-2)") (class "Default")
      (node (ref "R5") (pin "1") (pinfunction "1_1") (pintype "passive"))
      (node (ref "VR5") (pin "A2") (pinfunction "2_A2") (pintype "bidirectional"))
    )
    (net (code "54") (name "Net-(VR5A-3)") (class "Default")
      (node (ref "R28") (pin "2") (pinfunction "2_2") (pintype "passive"))
      (node (ref "R31") (pin "2") (pinfunction "2_2") (pintype "passive"))
      (node (ref "R32") (pin "2") (pinfunction "2_2") (pintype "passive"))
      (node (ref "R34") (pin "2") (pinfunction "2_2") (pintype "passive"))
      (node (ref "VR5") (pin "A3") (pinfunction "3_A3") (pintype "bidirectional"))
    )
    (net (code "55") (name "Net-(VR5B-2)") (class "Default")
      (node (ref "R6") (pin "1") (pinfunction "1_1") (pintype "passive"))
      (node (ref "VR5") (pin "B2") (pinfunction "2_B2") (pintype "bidirectional"))
    )
    (net (code "56") (name "Net-(VR5B-3)") (class "Default")
      (node (ref "R29") (pin "2") (pinfunction "2_2") (pintype "passive"))
      (node (ref "R30") (pin "2") (pinfunction "2_2") (pintype "passive"))
      (node (ref "R33") (pin "2") (pinfunction "2_2") (pintype "passive"))
      (node (ref "R35") (pin "2") (pinfunction "2_2") (pintype "passive"))
      (node (ref "VR5") (pin "B3") (pinfunction "3_B3") (pintype "bidirectional"))
    )
    (net (code "57") (name "OUTL") (class "Default")
      (node (ref "C18") (pin "-") (pinfunction "-_-") (pintype "passive"))
      (node (ref "X5") (pin "2") (pinfunction "2_2") (pintype "bidirectional"))
    )
    (net (code "58") (name "OUTR") (class "Default")
      (node (ref "C19") (pin "-") (pinfunction "-_-") (pintype "passive"))
      (node (ref "X5") (pin "3") (pinfunction "3_3") (pintype "bidirectional"))
    )
    (net (code "59") (name "PGND") (class "Default")
      (node (ref "C7") (pin "1") (pinfunction "1_1") (pintype "passive"))
      (node (ref "R3") (pin "1") (pinfunction "1_1") (pintype "passive"))
      (node (ref "R4") (pin "2") (pinfunction "2_2") (pintype "passive"))
      (node (ref "T1") (pin "B1") (pinfunction "B1_B1") (pintype "bidirectional"))
      (node (ref "T2") (pin "B1") (pinfunction "B1_B1") (pintype "bidirectional"))
      (node (ref "T3") (pin "B1") (pinfunction "B1_B1") (pintype "bidirectional"))
      (node (ref "T4") (pin "B1") (pinfunction "B1_B1") (pintype "bidirectional"))
      (node (ref "T5") (pin "B1") (pinfunction "B1_B1") (pintype "bidirectional"))
      (node (ref "T6") (pin "B1") (pinfunction "B1_B1") (pintype "bidirectional"))
      (node (ref "T7") (pin "B1") (pinfunction "B1_B1") (pintype "bidirectional"))
      (node (ref "T8") (pin "B1") (pinfunction "B1_B1") (pintype "bidirectional"))
      (node (ref "TP1") (pin "1") (pinfunction "P$1_1") (pintype "bidirectional"))
      (node (ref "U1") (pin "10") (pinfunction "IN+_10") (pintype "bidirectional"))
      (node (ref "U1") (pin "12") (pinfunction "IN+_12") (pintype "bidirectional"))
      (node (ref "U1") (pin "3") (pinfunction "IN+_3") (pintype "bidirectional"))
      (node (ref "U1") (pin "5") (pinfunction "IN+_5") (pintype "bidirectional"))
      (node (ref "U2") (pin "10") (pinfunction "IN+_10") (pintype "bidirectional"))
      (node (ref "U2") (pin "12") (pinfunction "IN+_12") (pintype "bidirectional"))
      (node (ref "U2") (pin "3") (pinfunction "IN+_3") (pintype "bidirectional"))
      (node (ref "U2") (pin "5") (pinfunction "IN+_5") (pintype "bidirectional"))
      (node (ref "VR1") (pin "A1") (pinfunction "1_A1") (pintype "bidirectional"))
      (node (ref "VR1") (pin "B1") (pinfunction "1_B1") (pintype "bidirectional"))
      (node (ref "VR2") (pin "A1") (pinfunction "1_A1") (pintype "bidirectional"))
      (node (ref "VR2") (pin "B1") (pinfunction "1_B1") (pintype "bidirectional"))
      (node (ref "VR3") (pin "A1") (pinfunction "1_A1") (pintype "bidirectional"))
      (node (ref "VR3") (pin "B1") (pinfunction "1_B1") (pintype "bidirectional"))
      (node (ref "VR4") (pin "A1") (pinfunction "1_A1") (pintype "bidirectional"))
      (node (ref "VR4") (pin "B1") (pinfunction "1_B1") (pintype "bidirectional"))
      (node (ref "VR5") (pin "A1") (pinfunction "1_A1") (pintype "bidirectional"))
      (node (ref "VR5") (pin "B1") (pinfunction "1_B1") (pintype "bidirectional"))
    )
    (net (code "60") (name "VCC") (class "Default")
      (node (ref "C4") (pin "1") (pinfunction "1_1") (pintype "passive"))
      (node (ref "C5") (pin "1") (pinfunction "1_1") (pintype "passive"))
      (node (ref "C6") (pin "+") (pinfunction "+_+") (pintype "passive"))
      (node (ref "R3") (pin "2") (pinfunction "2_2") (pintype "passive"))
      (node (ref "R38") (pin "2") (pinfunction "2_2") (pintype "passive"))
      (node (ref "U1") (pin "4") (pinfunction "VCC_4") (pintype "bidirectional"))
      (node (ref "U2") (pin "4") (pinfunction "VCC_4") (pintype "bidirectional"))
      (node (ref "U3") (pin "2") (pinfunction "OUT_2") (pintype "bidirectional"))
      (node (ref "U3") (pin "4") (pinfunction "OUT_4") (pintype "bidirectional"))
      (node (ref "X6") (pin "1") (pinfunction "1_1") (pintype "passive"))
    )
    (net (code "61") (name "unconnected-(J1-CDN-Pad-2)") (class "Default")
      (node (ref "J1") (pin "-2") (pinfunction "CDN_-2") (pintype "bidirectional"))
    )
  )
)
